# sensor_a2.net
KiCad netlist of a schematic drawn in EAGLE
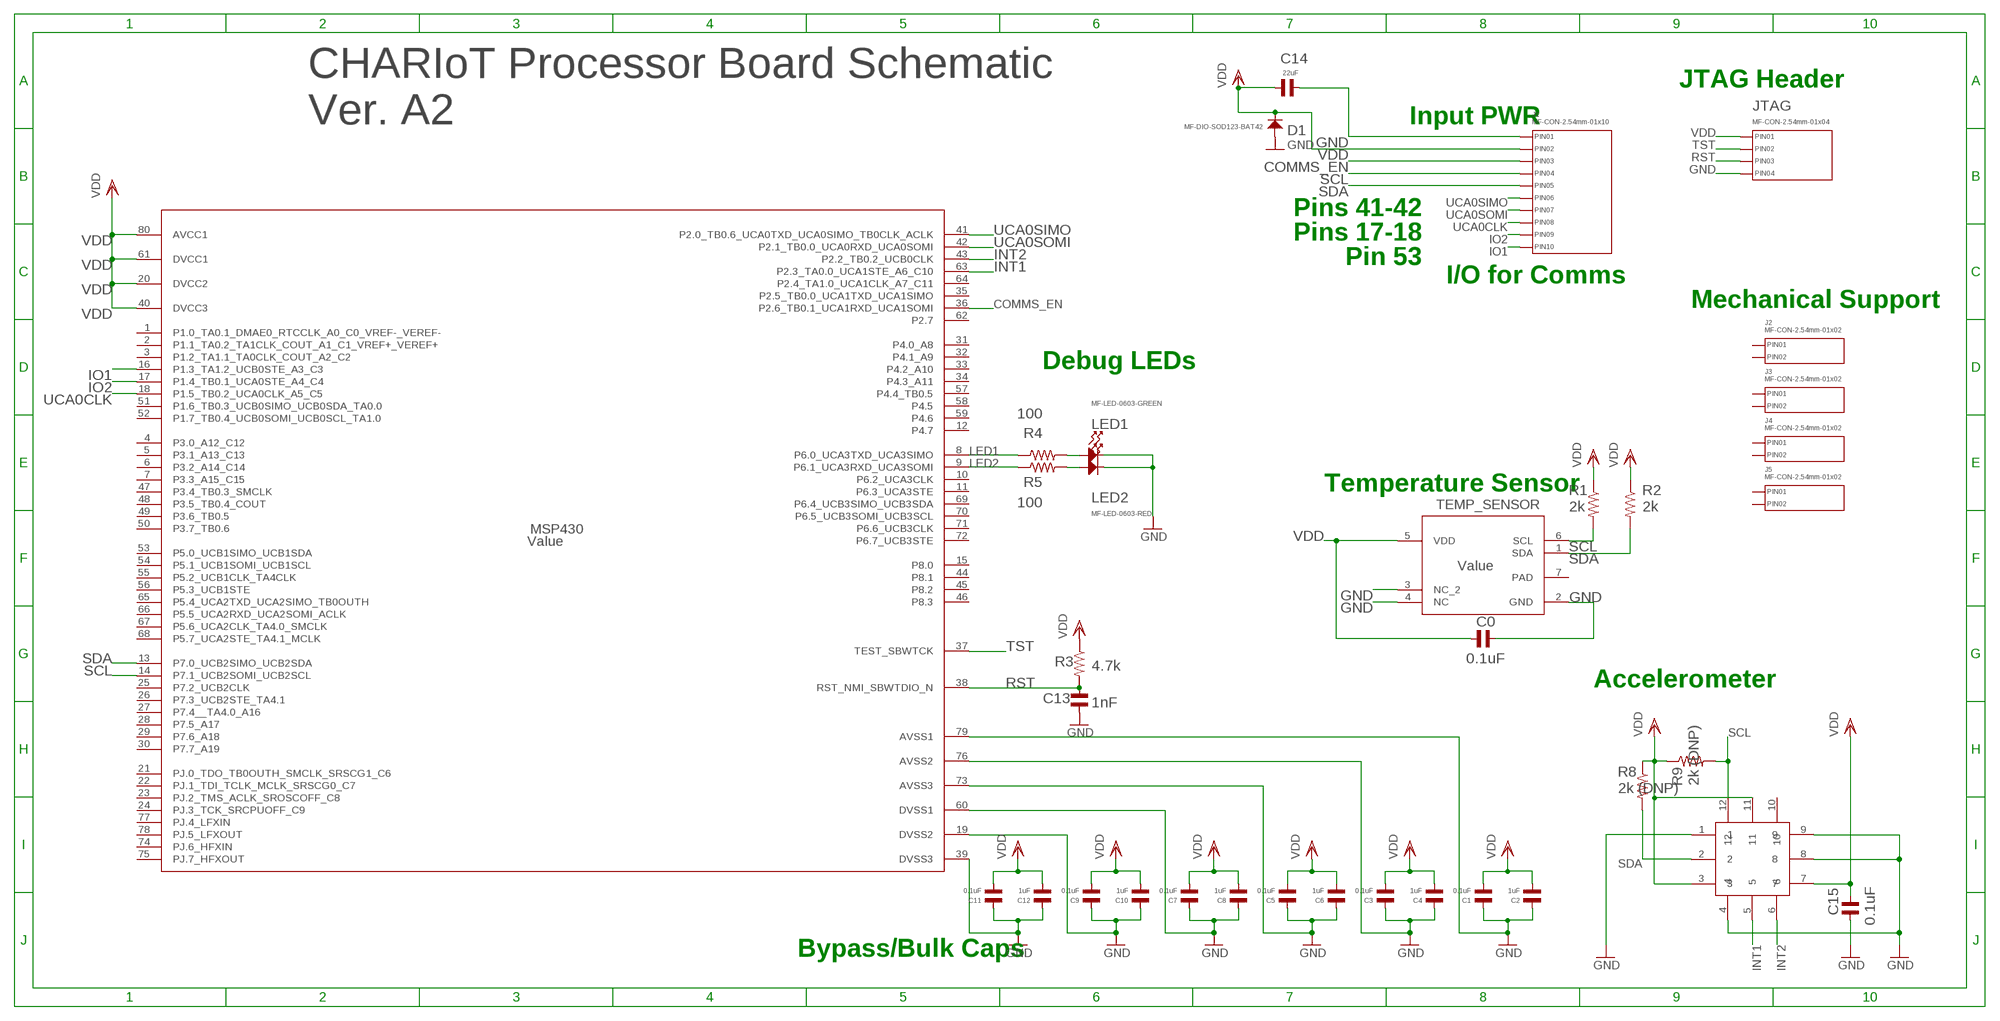
[diagram p0: schematic, sheet 1]

(export (version "E")
  (design (tool "Eeschema 10.0.6"))
  (components
    (comp (ref "ACCEL")
      (value "BMA253")
      (footprint "eagle-import:LGA-12")
      (libsource (lib "eagle-import") (part "BMA253"))
    )
    (comp (ref "C0")
      (value "0.1uF")
      (footprint "eagle-import:C0603")
      (libsource (lib "eagle-import") (part "CAPACITOR_NP_0603"))
    )
    (comp (ref "C1")
      (value "0.1uF")
      (footprint "eagle-import:C0603")
      (libsource (lib "eagle-import") (part "CAPACITOR_NP_0603"))
    )
    (comp (ref "C2")
      (value "1uF")
      (footprint "eagle-import:C0603")
      (libsource (lib "eagle-import") (part "CAPACITOR_NP_0603"))
    )
    (comp (ref "C3")
      (value "0.1uF")
      (footprint "eagle-import:C0603")
      (libsource (lib "eagle-import") (part "CAPACITOR_NP_0603"))
    )
    (comp (ref "C4")
      (value "1uF")
      (footprint "eagle-import:C0603")
      (libsource (lib "eagle-import") (part "CAPACITOR_NP_0603"))
    )
    (comp (ref "C5")
      (value "0.1uF")
      (footprint "eagle-import:C0603")
      (libsource (lib "eagle-import") (part "CAPACITOR_NP_0603"))
    )
    (comp (ref "C6")
      (value "1uF")
      (footprint "eagle-import:C0603")
      (libsource (lib "eagle-import") (part "CAPACITOR_NP_0603"))
    )
    (comp (ref "C7")
      (value "0.1uF")
      (footprint "eagle-import:C0603")
      (libsource (lib "eagle-import") (part "CAPACITOR_NP_0603"))
    )
    (comp (ref "C8")
      (value "1uF")
      (footprint "eagle-import:C0603")
      (libsource (lib "eagle-import") (part "CAPACITOR_NP_0603"))
    )
    (comp (ref "C9")
      (value "0.1uF")
      (footprint "eagle-import:C0603")
      (libsource (lib "eagle-import") (part "CAPACITOR_NP_0603"))
    )
    (comp (ref "C10")
      (value "1uF")
      (footprint "eagle-import:C0603")
      (libsource (lib "eagle-import") (part "CAPACITOR_NP_0603"))
    )
    (comp (ref "C11")
      (value "0.1uF")
      (footprint "eagle-import:C0603")
      (libsource (lib "eagle-import") (part "CAPACITOR_NP_0603"))
    )
    (comp (ref "C12")
      (value "1uF")
      (footprint "eagle-import:C0603")
      (libsource (lib "eagle-import") (part "CAPACITOR_NP_0603"))
    )
    (comp (ref "C13")
      (value "1nF")
      (footprint "eagle-import:C0603")
      (libsource (lib "eagle-import") (part "CAPACITOR_NP_0603"))
    )
    (comp (ref "C14")
      (value "22uF")
      (footprint "eagle-import:C0603")
      (libsource (lib "eagle-import") (part "CAPACITOR_NP_0603"))
    )
    (comp (ref "C15")
      (value "0.1uF")
      (footprint "eagle-import:C0603")
      (libsource (lib "eagle-import") (part "CAPACITOR_NP_0603"))
    )
    (comp (ref "D1")
      (value "MF-DIO-SOD123-BAT42")
      (footprint "eagle-import:SOD-123")
      (fields (field (name "HOUSEPART") "YES"))
      (libsource (lib "eagle-import") (part "DIODES_SOD-123_BAT42"))
    )
    (comp (ref "J1")
      (value "MF-CON-2.54mm-01x10")
      (footprint "eagle-import:PTH_2.54MM_01X10")
      (fields (field (name "HOUSEPART") "YES"))
      (libsource (lib "eagle-import") (part "CON_01X10_PTH_2.54MM"))
    )
    (comp (ref "J2")
      (value "MF-CON-2.54mm-01x02")
      (footprint "eagle-import:PTH_2.54MM_01X02")
      (fields (field (name "HOUSEPART") "YES"))
      (libsource (lib "eagle-import") (part "CON_01X02_PTH_2.54MM"))
    )
    (comp (ref "J3")
      (value "MF-CON-2.54mm-01x02")
      (footprint "eagle-import:PTH_2.54MM_01X02")
      (fields (field (name "HOUSEPART") "YES"))
      (libsource (lib "eagle-import") (part "CON_01X02_PTH_2.54MM"))
    )
    (comp (ref "J4")
      (value "MF-CON-2.54mm-01x02")
      (footprint "eagle-import:PTH_2.54MM_01X02")
      (fields (field (name "HOUSEPART") "YES"))
      (libsource (lib "eagle-import") (part "CON_01X02_PTH_2.54MM"))
    )
    (comp (ref "J5")
      (value "MF-CON-2.54mm-01x02")
      (footprint "eagle-import:PTH_2.54MM_01X02")
      (fields (field (name "HOUSEPART") "YES"))
      (libsource (lib "eagle-import") (part "CON_01X02_PTH_2.54MM"))
    )
    (comp (ref "JTAG")
      (value "MF-CON-2.54mm-01x04")
      (footprint "eagle-import:PTH_2.54MM_01X04")
      (fields (field (name "HOUSEPART") "YES"))
      (libsource (lib "eagle-import") (part "CON_01X04_PTH_2.54MM"))
    )
    (comp (ref "LED1")
      (value "MF-LED-0603-GREEN")
      (footprint "eagle-import:LED0603")
      (fields (field (name "HOUSEPART") "YES"))
      (libsource (lib "eagle-import") (part "LED_SINGLE-0603-GREEN"))
    )
    (comp (ref "LED2")
      (value "MF-LED-0603-RED")
      (footprint "eagle-import:LED0603")
      (fields (field (name "HOUSEPART") "YES"))
      (libsource (lib "eagle-import") (part "LED_SINGLE-0603-RED"))
    )
    (comp (ref "MSP430")
      (value "Value")
      (footprint "eagle-import:PN0080A_N")
      (fields
        (field (name "MANUFACTURER") "Texas Instruments")
        (field (name "PARTNUMBER") "MSP430FR5994IPNR")
      )
      (libsource (lib "eagle-import") (part "MSP430FR5994IPNR"))
    )
    (comp (ref "R1")
      (value "2k")
      (footprint "eagle-import:R0603")
      (libsource (lib "eagle-import") (part "RESISTOR_0603"))
    )
    (comp (ref "R2")
      (value "2k")
      (footprint "eagle-import:R0603")
      (libsource (lib "eagle-import") (part "RESISTOR_0603"))
    )
    (comp (ref "R3")
      (value "4.7k")
      (footprint "eagle-import:R0603")
      (libsource (lib "eagle-import") (part "RESISTOR_0603"))
    )
    (comp (ref "R4")
      (value "100")
      (footprint "eagle-import:R0603")
      (libsource (lib "eagle-import") (part "RESISTOR_0603"))
    )
    (comp (ref "R5")
      (value "100")
      (footprint "eagle-import:R0603")
      (libsource (lib "eagle-import") (part "RESISTOR_0603"))
    )
    (comp (ref "R8")
      (value "2k (DNP)")
      (footprint "eagle-import:R0603")
      (libsource (lib "eagle-import") (part "RESISTOR_0603"))
    )
    (comp (ref "R9")
      (value "2k (DNP)")
      (footprint "eagle-import:R0603")
      (libsource (lib "eagle-import") (part "RESISTOR_0603"))
    )
    (comp (ref "TEMP_SENSOR")
      (value "Value")
      (footprint "eagle-import:DMB0006A")
      (fields
        (field (name "ALTERNATEPARTNUMBER") "HDC1080DMBT")
        (field (name "MANUFACTURER") "Texas Instruments")
        (field (name "PARTNUMBER") "HDC1080DMBR")
      )
      (libsource (lib "eagle-import") (part "HDC1080DMBR"))
    )
  )
  (nets
    (net (code "1") (name "/COMMS_EN") (class "Default")
      (node (ref "J1") (pin "P$3") (pinfunction "PIN3_P$3") (pintype "bidirectional"))
      (node (ref "MSP430") (pin "36") (pinfunction "P2.6_TB0.1_UCA1RXD_UCA1SOMI_36") (pintype "bidirectional"))
    )
    (net (code "2") (name "/INT1") (class "Default")
      (node (ref "ACCEL") (pin "5") (pinfunction "5_5") (pintype "bidirectional"))
      (node (ref "MSP430") (pin "63") (pinfunction "P2.3_TA0.0_UCA1STE_A6_C10_63") (pintype "bidirectional"))
    )
    (net (code "3") (name "/INT2") (class "Default")
      (node (ref "ACCEL") (pin "6") (pinfunction "6_6") (pintype "bidirectional"))
      (node (ref "MSP430") (pin "43") (pinfunction "P2.2_TB0.2_UCB0CLK_43") (pintype "bidirectional"))
    )
    (net (code "4") (name "/IO1") (class "Default")
      (node (ref "J1") (pin "P$10") (pinfunction "PIN10_P$10") (pintype "bidirectional"))
      (node (ref "MSP430") (pin "16") (pinfunction "P1.3_TA1.2_UCB0STE_A3_C3_16") (pintype "bidirectional"))
    )
    (net (code "5") (name "/IO2") (class "Default")
      (node (ref "J1") (pin "P$9") (pinfunction "PIN9_P$9") (pintype "bidirectional"))
      (node (ref "MSP430") (pin "17") (pinfunction "P1.4_TB0.1_UCA0STE_A4_C4_17") (pintype "bidirectional"))
    )
    (net (code "6") (name "/LED1") (class "Default")
      (node (ref "MSP430") (pin "8") (pinfunction "P6.0_UCA3TXD_UCA3SIMO_8") (pintype "bidirectional"))
      (node (ref "R4") (pin "P$1") (pinfunction "P$1_P$1") (pintype "passive"))
    )
    (net (code "7") (name "/LED2") (class "Default")
      (node (ref "MSP430") (pin "9") (pinfunction "P6.1_UCA3RXD_UCA3SOMI_9") (pintype "bidirectional"))
      (node (ref "R5") (pin "P$1") (pinfunction "P$1_P$1") (pintype "passive"))
    )
    (net (code "8") (name "/PAD") (class "Default")
      (node (ref "TEMP_SENSOR") (pin "7") (pinfunction "PAD_7") (pintype "power_in"))
    )
    (net (code "9") (name "/RST") (class "Default")
      (node (ref "C13") (pin "P$1") (pinfunction "P$1_P$1") (pintype "passive"))
      (node (ref "JTAG") (pin "P$3") (pinfunction "PIN3_P$3") (pintype "bidirectional"))
      (node (ref "MSP430") (pin "38") (pinfunction "RST_NMI_SBWTDIO_N_38") (pintype "bidirectional"))
      (node (ref "R3") (pin "P$2") (pinfunction "P$2_P$2") (pintype "passive"))
    )
    (net (code "10") (name "/SCL") (class "Default")
      (node (ref "ACCEL") (pin "12") (pinfunction "12_12") (pintype "bidirectional"))
      (node (ref "J1") (pin "P$4") (pinfunction "PIN4_P$4") (pintype "bidirectional"))
      (node (ref "MSP430") (pin "14") (pinfunction "P7.1_UCB2SOMI_UCB2SCL_14") (pintype "bidirectional"))
      (node (ref "R1") (pin "P$2") (pinfunction "P$2_P$2") (pintype "passive"))
      (node (ref "R9") (pin "P$2") (pinfunction "P$2_P$2") (pintype "passive"))
      (node (ref "TEMP_SENSOR") (pin "6") (pinfunction "SCL_6") (pintype "open_collector"))
    )
    (net (code "11") (name "/SDA") (class "Default")
      (node (ref "ACCEL") (pin "2") (pinfunction "2_2") (pintype "bidirectional"))
      (node (ref "J1") (pin "P$5") (pinfunction "PIN5_P$5") (pintype "bidirectional"))
      (node (ref "MSP430") (pin "13") (pinfunction "P7.0_UCB2SIMO_UCB2SDA_13") (pintype "bidirectional"))
      (node (ref "R2") (pin "P$2") (pinfunction "P$2_P$2") (pintype "passive"))
      (node (ref "R8") (pin "P$2") (pinfunction "P$2_P$2") (pintype "passive"))
      (node (ref "TEMP_SENSOR") (pin "1") (pinfunction "SDA_1") (pintype "bidirectional"))
    )
    (net (code "12") (name "/TST") (class "Default")
      (node (ref "JTAG") (pin "P$2") (pinfunction "PIN2_P$2") (pintype "bidirectional"))
      (node (ref "MSP430") (pin "37") (pinfunction "TEST_SBWTCK_37") (pintype "input"))
    )
    (net (code "13") (name "/UCA0CLK") (class "Default")
      (node (ref "J1") (pin "P$8") (pinfunction "PIN8_P$8") (pintype "bidirectional"))
      (node (ref "MSP430") (pin "18") (pinfunction "P1.5_TB0.2_UCA0CLK_A5_C5_18") (pintype "bidirectional"))
    )
    (net (code "14") (name "/UCA0SIMO") (class "Default")
      (node (ref "J1") (pin "P$6") (pinfunction "PIN6_P$6") (pintype "bidirectional"))
      (node (ref "MSP430") (pin "41") (pinfunction "P2.0_TB0.6_UCA0TXD_UCA0SIMO_TB0CLK_ACLK_41") (pintype "bidirectional"))
    )
    (net (code "15") (name "/UCA0SOMI") (class "Default")
      (node (ref "J1") (pin "P$7") (pinfunction "PIN7_P$7") (pintype "bidirectional"))
      (node (ref "MSP430") (pin "42") (pinfunction "P2.1_TB0.0_UCA0RXD_UCA0SOMI_42") (pintype "bidirectional"))
    )
    (net (code "16") (name "GND") (class "Default")
      (node (ref "ACCEL") (pin "1") (pinfunction "1_1") (pintype "bidirectional"))
      (node (ref "ACCEL") (pin "4") (pinfunction "4_4") (pintype "bidirectional"))
      (node (ref "ACCEL") (pin "8") (pinfunction "8_8") (pintype "power_in"))
      (node (ref "ACCEL") (pin "9") (pinfunction "9_9") (pintype "power_in"))
      (node (ref "C0") (pin "P$2") (pinfunction "P$2_P$2") (pintype "passive"))
      (node (ref "C1") (pin "P$1") (pinfunction "P$1_P$1") (pintype "passive"))
      (node (ref "C10") (pin "P$1") (pinfunction "P$1_P$1") (pintype "passive"))
      (node (ref "C11") (pin "P$1") (pinfunction "P$1_P$1") (pintype "passive"))
      (node (ref "C12") (pin "P$1") (pinfunction "P$1_P$1") (pintype "passive"))
      (node (ref "C13") (pin "P$2") (pinfunction "P$2_P$2") (pintype "passive"))
      (node (ref "C14") (pin "P$2") (pinfunction "P$2_P$2") (pintype "passive"))
      (node (ref "C15") (pin "P$1") (pinfunction "P$1_P$1") (pintype "passive"))
      (node (ref "C2") (pin "P$1") (pinfunction "P$1_P$1") (pintype "passive"))
      (node (ref "C3") (pin "P$1") (pinfunction "P$1_P$1") (pintype "passive"))
      (node (ref "C4") (pin "P$1") (pinfunction "P$1_P$1") (pintype "passive"))
      (node (ref "C5") (pin "P$1") (pinfunction "P$1_P$1") (pintype "passive"))
      (node (ref "C6") (pin "P$1") (pinfunction "P$1_P$1") (pintype "passive"))
      (node (ref "C7") (pin "P$1") (pinfunction "P$1_P$1") (pintype "passive"))
      (node (ref "C8") (pin "P$1") (pinfunction "P$1_P$1") (pintype "passive"))
      (node (ref "C9") (pin "P$1") (pinfunction "P$1_P$1") (pintype "passive"))
      (node (ref "D1") (pin "ANODE") (pinfunction "ANODE_ANODE") (pintype "bidirectional"))
      (node (ref "J1") (pin "P$1") (pinfunction "PIN1_P$1") (pintype "bidirectional"))
      (node (ref "JTAG") (pin "P$4") (pinfunction "PIN4_P$4") (pintype "bidirectional"))
      (node (ref "LED1") (pin "CATHODE") (pinfunction "CATHODE_CATHODE") (pintype "power_in"))
      (node (ref "LED2") (pin "CATHODE") (pinfunction "CATHODE_CATHODE") (pintype "power_in"))
      (node (ref "MSP430") (pin "19") (pinfunction "DVSS2_19") (pintype "power_in"))
      (node (ref "MSP430") (pin "39") (pinfunction "DVSS3_39") (pintype "power_in"))
      (node (ref "MSP430") (pin "60") (pinfunction "DVSS1_60") (pintype "power_in"))
      (node (ref "MSP430") (pin "73") (pinfunction "AVSS3_73") (pintype "power_in"))
      (node (ref "MSP430") (pin "76") (pinfunction "AVSS2_76") (pintype "power_in"))
      (node (ref "MSP430") (pin "79") (pinfunction "AVSS1_79") (pintype "power_in"))
      (node (ref "TEMP_SENSOR") (pin "2") (pinfunction "GND_2") (pintype "power_in"))
      (node (ref "TEMP_SENSOR") (pin "3") (pinfunction "NC_2_3") (pintype "passive"))
      (node (ref "TEMP_SENSOR") (pin "4") (pinfunction "NC_4") (pintype "passive"))
    )
    (net (code "17") (name "Net-(LED1-PadANODE)") (class "Default")
      (node (ref "LED1") (pin "ANODE") (pinfunction "ANODE_ANODE") (pintype "power_in"))
      (node (ref "R4") (pin "P$2") (pinfunction "P$2_P$2") (pintype "passive"))
    )
    (net (code "18") (name "Net-(LED2-PadANODE)") (class "Default")
      (node (ref "LED2") (pin "ANODE") (pinfunction "ANODE_ANODE") (pintype "power_in"))
      (node (ref "R5") (pin "P$2") (pinfunction "P$2_P$2") (pintype "passive"))
    )
    (net (code "19") (name "VDD") (class "Default")
      (node (ref "ACCEL") (pin "11") (pinfunction "11_11") (pintype "bidirectional"))
      (node (ref "ACCEL") (pin "3") (pinfunction "3_3") (pintype "power_in"))
      (node (ref "ACCEL") (pin "7") (pinfunction "7_7") (pintype "power_in"))
      (node (ref "C0") (pin "P$1") (pinfunction "P$1_P$1") (pintype "passive"))
      (node (ref "C1") (pin "P$2") (pinfunction "P$2_P$2") (pintype "passive"))
      (node (ref "C10") (pin "P$2") (pinfunction "P$2_P$2") (pintype "passive"))
      (node (ref "C11") (pin "P$2") (pinfunction "P$2_P$2") (pintype "passive"))
      (node (ref "C12") (pin "P$2") (pinfunction "P$2_P$2") (pintype "passive"))
      (node (ref "C14") (pin "P$1") (pinfunction "P$1_P$1") (pintype "passive"))
      (node (ref "C15") (pin "P$2") (pinfunction "P$2_P$2") (pintype "passive"))
      (node (ref "C2") (pin "P$2") (pinfunction "P$2_P$2") (pintype "passive"))
      (node (ref "C3") (pin "P$2") (pinfunction "P$2_P$2") (pintype "passive"))
      (node (ref "C4") (pin "P$2") (pinfunction "P$2_P$2") (pintype "passive"))
      (node (ref "C5") (pin "P$2") (pinfunction "P$2_P$2") (pintype "passive"))
      (node (ref "C6") (pin "P$2") (pinfunction "P$2_P$2") (pintype "passive"))
      (node (ref "C7") (pin "P$2") (pinfunction "P$2_P$2") (pintype "passive"))
      (node (ref "C8") (pin "P$2") (pinfunction "P$2_P$2") (pintype "passive"))
      (node (ref "C9") (pin "P$2") (pinfunction "P$2_P$2") (pintype "passive"))
      (node (ref "D1") (pin "CATHODE") (pinfunction "CATHODE_CATHODE") (pintype "bidirectional"))
      (node (ref "J1") (pin "P$2") (pinfunction "PIN2_P$2") (pintype "bidirectional"))
      (node (ref "JTAG") (pin "P$1") (pinfunction "PIN1_P$1") (pintype "bidirectional"))
      (node (ref "MSP430") (pin "20") (pinfunction "DVCC2_20") (pintype "power_in"))
      (node (ref "MSP430") (pin "40") (pinfunction "DVCC3_40") (pintype "power_in"))
      (node (ref "MSP430") (pin "61") (pinfunction "DVCC1_61") (pintype "power_in"))
      (node (ref "MSP430") (pin "80") (pinfunction "AVCC1_80") (pintype "power_in"))
      (node (ref "R1") (pin "P$1") (pinfunction "P$1_P$1") (pintype "passive"))
      (node (ref "R2") (pin "P$1") (pinfunction "P$1_P$1") (pintype "passive"))
      (node (ref "R3") (pin "P$1") (pinfunction "P$1_P$1") (pintype "passive"))
      (node (ref "R8") (pin "P$1") (pinfunction "P$1_P$1") (pintype "passive"))
      (node (ref "R9") (pin "P$1") (pinfunction "P$1_P$1") (pintype "passive"))
      (node (ref "TEMP_SENSOR") (pin "5") (pinfunction "VDD_5") (pintype "power_in"))
    )
    (net (code "20") (name "unconnected-(ACCEL-Pad10)") (class "Default")
      (node (ref "ACCEL") (pin "10") (pinfunction "10_10") (pintype "bidirectional"))
    )
    (net (code "21") (name "unconnected-(J2-PIN1-PadP$1)") (class "Default")
      (node (ref "J2") (pin "P$1") (pinfunction "PIN1_P$1") (pintype "bidirectional"))
    )
    (net (code "22") (name "unconnected-(J2-PIN2-PadP$2)") (class "Default")
      (node (ref "J2") (pin "P$2") (pinfunction "PIN2_P$2") (pintype "bidirectional"))
    )
    (net (code "23") (name "unconnected-(J3-PIN1-PadP$1)") (class "Default")
      (node (ref "J3") (pin "P$1") (pinfunction "PIN1_P$1") (pintype "bidirectional"))
    )
    (net (code "24") (name "unconnected-(J3-PIN2-PadP$2)") (class "Default")
      (node (ref "J3") (pin "P$2") (pinfunction "PIN2_P$2") (pintype "bidirectional"))
    )
    (net (code "25") (name "unconnected-(J4-PIN1-PadP$1)") (class "Default")
      (node (ref "J4") (pin "P$1") (pinfunction "PIN1_P$1") (pintype "bidirectional"))
    )
    (net (code "26") (name "unconnected-(J4-PIN2-PadP$2)") (class "Default")
      (node (ref "J4") (pin "P$2") (pinfunction "PIN2_P$2") (pintype "bidirectional"))
    )
    (net (code "27") (name "unconnected-(J5-PIN1-PadP$1)") (class "Default")
      (node (ref "J5") (pin "P$1") (pinfunction "PIN1_P$1") (pintype "bidirectional"))
    )
    (net (code "28") (name "unconnected-(J5-PIN2-PadP$2)") (class "Default")
      (node (ref "J5") (pin "P$2") (pinfunction "PIN2_P$2") (pintype "bidirectional"))
    )
    (net (code "29") (name "unconnected-(MSP430-P1.0_TA0.1_DMAE0_RTCCLK_A0_C0_VREF-_VEREF--Pad1)") (class "Default")
      (node (ref "MSP430") (pin "1") (pinfunction "P1.0_TA0.1_DMAE0_RTCCLK_A0_C0_VREF-_VEREF-_1") (pintype "bidirectional"))
    )
    (net (code "30") (name "unconnected-(MSP430-P1.1_TA0.2_TA1CLK_COUT_A1_C1_VREF+_VEREF+-Pad2)") (class "Default")
      (node (ref "MSP430") (pin "2") (pinfunction "P1.1_TA0.2_TA1CLK_COUT_A1_C1_VREF+_VEREF+_2") (pintype "bidirectional"))
    )
    (net (code "31") (name "unconnected-(MSP430-P1.2_TA1.1_TA0CLK_COUT_A2_C2-Pad3)") (class "Default")
      (node (ref "MSP430") (pin "3") (pinfunction "P1.2_TA1.1_TA0CLK_COUT_A2_C2_3") (pintype "bidirectional"))
    )
    (net (code "32") (name "unconnected-(MSP430-P1.6_TB0.3_UCB0SIMO_UCB0SDA_TA0.0-Pad51)") (class "Default")
      (node (ref "MSP430") (pin "51") (pinfunction "P1.6_TB0.3_UCB0SIMO_UCB0SDA_TA0.0_51") (pintype "bidirectional"))
    )
    (net (code "33") (name "unconnected-(MSP430-P1.7_TB0.4_UCB0SOMI_UCB0SCL_TA1.0-Pad52)") (class "Default")
      (node (ref "MSP430") (pin "52") (pinfunction "P1.7_TB0.4_UCB0SOMI_UCB0SCL_TA1.0_52") (pintype "bidirectional"))
    )
    (net (code "34") (name "unconnected-(MSP430-P2.4_TA1.0_UCA1CLK_A7_C11-Pad64)") (class "Default")
      (node (ref "MSP430") (pin "64") (pinfunction "P2.4_TA1.0_UCA1CLK_A7_C11_64") (pintype "bidirectional"))
    )
    (net (code "35") (name "unconnected-(MSP430-P2.5_TB0.0_UCA1TXD_UCA1SIMO-Pad35)") (class "Default")
      (node (ref "MSP430") (pin "35") (pinfunction "P2.5_TB0.0_UCA1TXD_UCA1SIMO_35") (pintype "bidirectional"))
    )
    (net (code "36") (name "unconnected-(MSP430-P2.7-Pad62)") (class "Default")
      (node (ref "MSP430") (pin "62") (pinfunction "P2.7_62") (pintype "bidirectional"))
    )
    (net (code "37") (name "unconnected-(MSP430-P3.0_A12_C12-Pad4)") (class "Default")
      (node (ref "MSP430") (pin "4") (pinfunction "P3.0_A12_C12_4") (pintype "bidirectional"))
    )
    (net (code "38") (name "unconnected-(MSP430-P3.1_A13_C13-Pad5)") (class "Default")
      (node (ref "MSP430") (pin "5") (pinfunction "P3.1_A13_C13_5") (pintype "bidirectional"))
    )
    (net (code "39") (name "unconnected-(MSP430-P3.2_A14_C14-Pad6)") (class "Default")
      (node (ref "MSP430") (pin "6") (pinfunction "P3.2_A14_C14_6") (pintype "bidirectional"))
    )
    (net (code "40") (name "unconnected-(MSP430-P3.3_A15_C15-Pad7)") (class "Default")
      (node (ref "MSP430") (pin "7") (pinfunction "P3.3_A15_C15_7") (pintype "bidirectional"))
    )
    (net (code "41") (name "unconnected-(MSP430-P3.4_TB0.3_SMCLK-Pad47)") (class "Default")
      (node (ref "MSP430") (pin "47") (pinfunction "P3.4_TB0.3_SMCLK_47") (pintype "bidirectional"))
    )
    (net (code "42") (name "unconnected-(MSP430-P3.5_TB0.4_COUT-Pad48)") (class "Default")
      (node (ref "MSP430") (pin "48") (pinfunction "P3.5_TB0.4_COUT_48") (pintype "bidirectional"))
    )
    (net (code "43") (name "unconnected-(MSP430-P3.6_TB0.5-Pad49)") (class "Default")
      (node (ref "MSP430") (pin "49") (pinfunction "P3.6_TB0.5_49") (pintype "bidirectional"))
    )
    (net (code "44") (name "unconnected-(MSP430-P3.7_TB0.6-Pad50)") (class "Default")
      (node (ref "MSP430") (pin "50") (pinfunction "P3.7_TB0.6_50") (pintype "bidirectional"))
    )
    (net (code "45") (name "unconnected-(MSP430-P4.0_A8-Pad31)") (class "Default")
      (node (ref "MSP430") (pin "31") (pinfunction "P4.0_A8_31") (pintype "bidirectional"))
    )
    (net (code "46") (name "unconnected-(MSP430-P4.1_A9-Pad32)") (class "Default")
      (node (ref "MSP430") (pin "32") (pinfunction "P4.1_A9_32") (pintype "bidirectional"))
    )
    (net (code "47") (name "unconnected-(MSP430-P4.2_A10-Pad33)") (class "Default")
      (node (ref "MSP430") (pin "33") (pinfunction "P4.2_A10_33") (pintype "bidirectional"))
    )
    (net (code "48") (name "unconnected-(MSP430-P4.3_A11-Pad34)") (class "Default")
      (node (ref "MSP430") (pin "34") (pinfunction "P4.3_A11_34") (pintype "bidirectional"))
    )
    (net (code "49") (name "unconnected-(MSP430-P4.4_TB0.5-Pad57)") (class "Default")
      (node (ref "MSP430") (pin "57") (pinfunction "P4.4_TB0.5_57") (pintype "bidirectional"))
    )
    (net (code "50") (name "unconnected-(MSP430-P4.5-Pad58)") (class "Default")
      (node (ref "MSP430") (pin "58") (pinfunction "P4.5_58") (pintype "bidirectional"))
    )
    (net (code "51") (name "unconnected-(MSP430-P4.6-Pad59)") (class "Default")
      (node (ref "MSP430") (pin "59") (pinfunction "P4.6_59") (pintype "bidirectional"))
    )
    (net (code "52") (name "unconnected-(MSP430-P4.7-Pad12)") (class "Default")
      (node (ref "MSP430") (pin "12") (pinfunction "P4.7_12") (pintype "bidirectional"))
    )
    (net (code "53") (name "unconnected-(MSP430-P5.0_UCB1SIMO_UCB1SDA-Pad53)") (class "Default")
      (node (ref "MSP430") (pin "53") (pinfunction "P5.0_UCB1SIMO_UCB1SDA_53") (pintype "bidirectional"))
    )
    (net (code "54") (name "unconnected-(MSP430-P5.1_UCB1SOMI_UCB1SCL-Pad54)") (class "Default")
      (node (ref "MSP430") (pin "54") (pinfunction "P5.1_UCB1SOMI_UCB1SCL_54") (pintype "bidirectional"))
    )
    (net (code "55") (name "unconnected-(MSP430-P5.2_UCB1CLK_TA4CLK-Pad55)") (class "Default")
      (node (ref "MSP430") (pin "55") (pinfunction "P5.2_UCB1CLK_TA4CLK_55") (pintype "bidirectional"))
    )
    (net (code "56") (name "unconnected-(MSP430-P5.3_UCB1STE-Pad56)") (class "Default")
      (node (ref "MSP430") (pin "56") (pinfunction "P5.3_UCB1STE_56") (pintype "bidirectional"))
    )
    (net (code "57") (name "unconnected-(MSP430-P5.4_UCA2TXD_UCA2SIMO_TB0OUTH-Pad65)") (class "Default")
      (node (ref "MSP430") (pin "65") (pinfunction "P5.4_UCA2TXD_UCA2SIMO_TB0OUTH_65") (pintype "bidirectional"))
    )
    (net (code "58") (name "unconnected-(MSP430-P5.5_UCA2RXD_UCA2SOMI_ACLK-Pad66)") (class "Default")
      (node (ref "MSP430") (pin "66") (pinfunction "P5.5_UCA2RXD_UCA2SOMI_ACLK_66") (pintype "bidirectional"))
    )
    (net (code "59") (name "unconnected-(MSP430-P5.6_UCA2CLK_TA4.0_SMCLK-Pad67)") (class "Default")
      (node (ref "MSP430") (pin "67") (pinfunction "P5.6_UCA2CLK_TA4.0_SMCLK_67") (pintype "bidirectional"))
    )
    (net (code "60") (name "unconnected-(MSP430-P5.7_UCA2STE_TA4.1_MCLK-Pad68)") (class "Default")
      (node (ref "MSP430") (pin "68") (pinfunction "P5.7_UCA2STE_TA4.1_MCLK_68") (pintype "bidirectional"))
    )
    (net (code "61") (name "unconnected-(MSP430-P6.2_UCA3CLK-Pad10)") (class "Default")
      (node (ref "MSP430") (pin "10") (pinfunction "P6.2_UCA3CLK_10") (pintype "bidirectional"))
    )
    (net (code "62") (name "unconnected-(MSP430-P6.3_UCA3STE-Pad11)") (class "Default")
      (node (ref "MSP430") (pin "11") (pinfunction "P6.3_UCA3STE_11") (pintype "bidirectional"))
    )
    (net (code "63") (name "unconnected-(MSP430-P6.4_UCB3SIMO_UCB3SDA-Pad69)") (class "Default")
      (node (ref "MSP430") (pin "69") (pinfunction "P6.4_UCB3SIMO_UCB3SDA_69") (pintype "bidirectional"))
    )
    (net (code "64") (name "unconnected-(MSP430-P6.5_UCB3SOMI_UCB3SCL-Pad70)") (class "Default")
      (node (ref "MSP430") (pin "70") (pinfunction "P6.5_UCB3SOMI_UCB3SCL_70") (pintype "bidirectional"))
    )
    (net (code "65") (name "unconnected-(MSP430-P6.6_UCB3CLK-Pad71)") (class "Default")
      (node (ref "MSP430") (pin "71") (pinfunction "P6.6_UCB3CLK_71") (pintype "bidirectional"))
    )
    (net (code "66") (name "unconnected-(MSP430-P6.7_UCB3STE-Pad72)") (class "Default")
      (node (ref "MSP430") (pin "72") (pinfunction "P6.7_UCB3STE_72") (pintype "bidirectional"))
    )
    (net (code "67") (name "unconnected-(MSP430-P7.2_UCB2CLK-Pad25)") (class "Default")
      (node (ref "MSP430") (pin "25") (pinfunction "P7.2_UCB2CLK_25") (pintype "bidirectional"))
    )
    (net (code "68") (name "unconnected-(MSP430-P7.3_UCB2STE_TA4.1-Pad26)") (class "Default")
      (node (ref "MSP430") (pin "26") (pinfunction "P7.3_UCB2STE_TA4.1_26") (pintype "bidirectional"))
    )
    (net (code "69") (name "unconnected-(MSP430-P7.4__TA4.0_A16-Pad27)") (class "Default")
      (node (ref "MSP430") (pin "27") (pinfunction "P7.4__TA4.0_A16_27") (pintype "bidirectional"))
    )
    (net (code "70") (name "unconnected-(MSP430-P7.5_A17-Pad28)") (class "Default")
      (node (ref "MSP430") (pin "28") (pinfunction "P7.5_A17_28") (pintype "bidirectional"))
    )
    (net (code "71") (name "unconnected-(MSP430-P7.6_A18-Pad29)") (class "Default")
      (node (ref "MSP430") (pin "29") (pinfunction "P7.6_A18_29") (pintype "bidirectional"))
    )
    (net (code "72") (name "unconnected-(MSP430-P7.7_A19-Pad30)") (class "Default")
      (node (ref "MSP430") (pin "30") (pinfunction "P7.7_A19_30") (pintype "bidirectional"))
    )
    (net (code "73") (name "unconnected-(MSP430-P8.0-Pad15)") (class "Default")
      (node (ref "MSP430") (pin "15") (pinfunction "P8.0_15") (pintype "bidirectional"))
    )
    (net (code "74") (name "unconnected-(MSP430-P8.1-Pad44)") (class "Default")
      (node (ref "MSP430") (pin "44") (pinfunction "P8.1_44") (pintype "bidirectional"))
    )
    (net (code "75") (name "unconnected-(MSP430-P8.2-Pad45)") (class "Default")
      (node (ref "MSP430") (pin "45") (pinfunction "P8.2_45") (pintype "bidirectional"))
    )
    (net (code "76") (name "unconnected-(MSP430-P8.3-Pad46)") (class "Default")
      (node (ref "MSP430") (pin "46") (pinfunction "P8.3_46") (pintype "bidirectional"))
    )
    (net (code "77") (name "unconnected-(MSP430-PJ.0_TDO_TB0OUTH_SMCLK_SRSCG1_C6-Pad21)") (class "Default")
      (node (ref "MSP430") (pin "21") (pinfunction "PJ.0_TDO_TB0OUTH_SMCLK_SRSCG1_C6_21") (pintype "bidirectional"))
    )
    (net (code "78") (name "unconnected-(MSP430-PJ.1_TDI_TCLK_MCLK_SRSCG0_C7-Pad22)") (class "Default")
      (node (ref "MSP430") (pin "22") (pinfunction "PJ.1_TDI_TCLK_MCLK_SRSCG0_C7_22") (pintype "bidirectional"))
    )
    (net (code "79") (name "unconnected-(MSP430-PJ.2_TMS_ACLK_SROSCOFF_C8-Pad23)") (class "Default")
      (node (ref "MSP430") (pin "23") (pinfunction "PJ.2_TMS_ACLK_SROSCOFF_C8_23") (pintype "bidirectional"))
    )
    (net (code "80") (name "unconnected-(MSP430-PJ.3_TCK_SRCPUOFF_C9-Pad24)") (class "Default")
      (node (ref "MSP430") (pin "24") (pinfunction "PJ.3_TCK_SRCPUOFF_C9_24") (pintype "bidirectional"))
    )
    (net (code "81") (name "unconnected-(MSP430-PJ.4_LFXIN-Pad77)") (class "Default")
      (node (ref "MSP430") (pin "77") (pinfunction "PJ.4_LFXIN_77") (pintype "bidirectional"))
    )
    (net (code "82") (name "unconnected-(MSP430-PJ.5_LFXOUT-Pad78)") (class "Default")
      (node (ref "MSP430") (pin "78") (pinfunction "PJ.5_LFXOUT_78") (pintype "bidirectional"))
    )
    (net (code "83") (name "unconnected-(MSP430-PJ.6_HFXIN-Pad74)") (class "Default")
      (node (ref "MSP430") (pin "74") (pinfunction "PJ.6_HFXIN_74") (pintype "bidirectional"))
    )
    (net (code "84") (name "unconnected-(MSP430-PJ.7_HFXOUT-Pad75)") (class "Default")
      (node (ref "MSP430") (pin "75") (pinfunction "PJ.7_HFXOUT_75") (pintype "bidirectional"))
    )
  )
)
